# PLD_Controller_Board.net
KiCad netlist of a schematic drawn in EAGLE
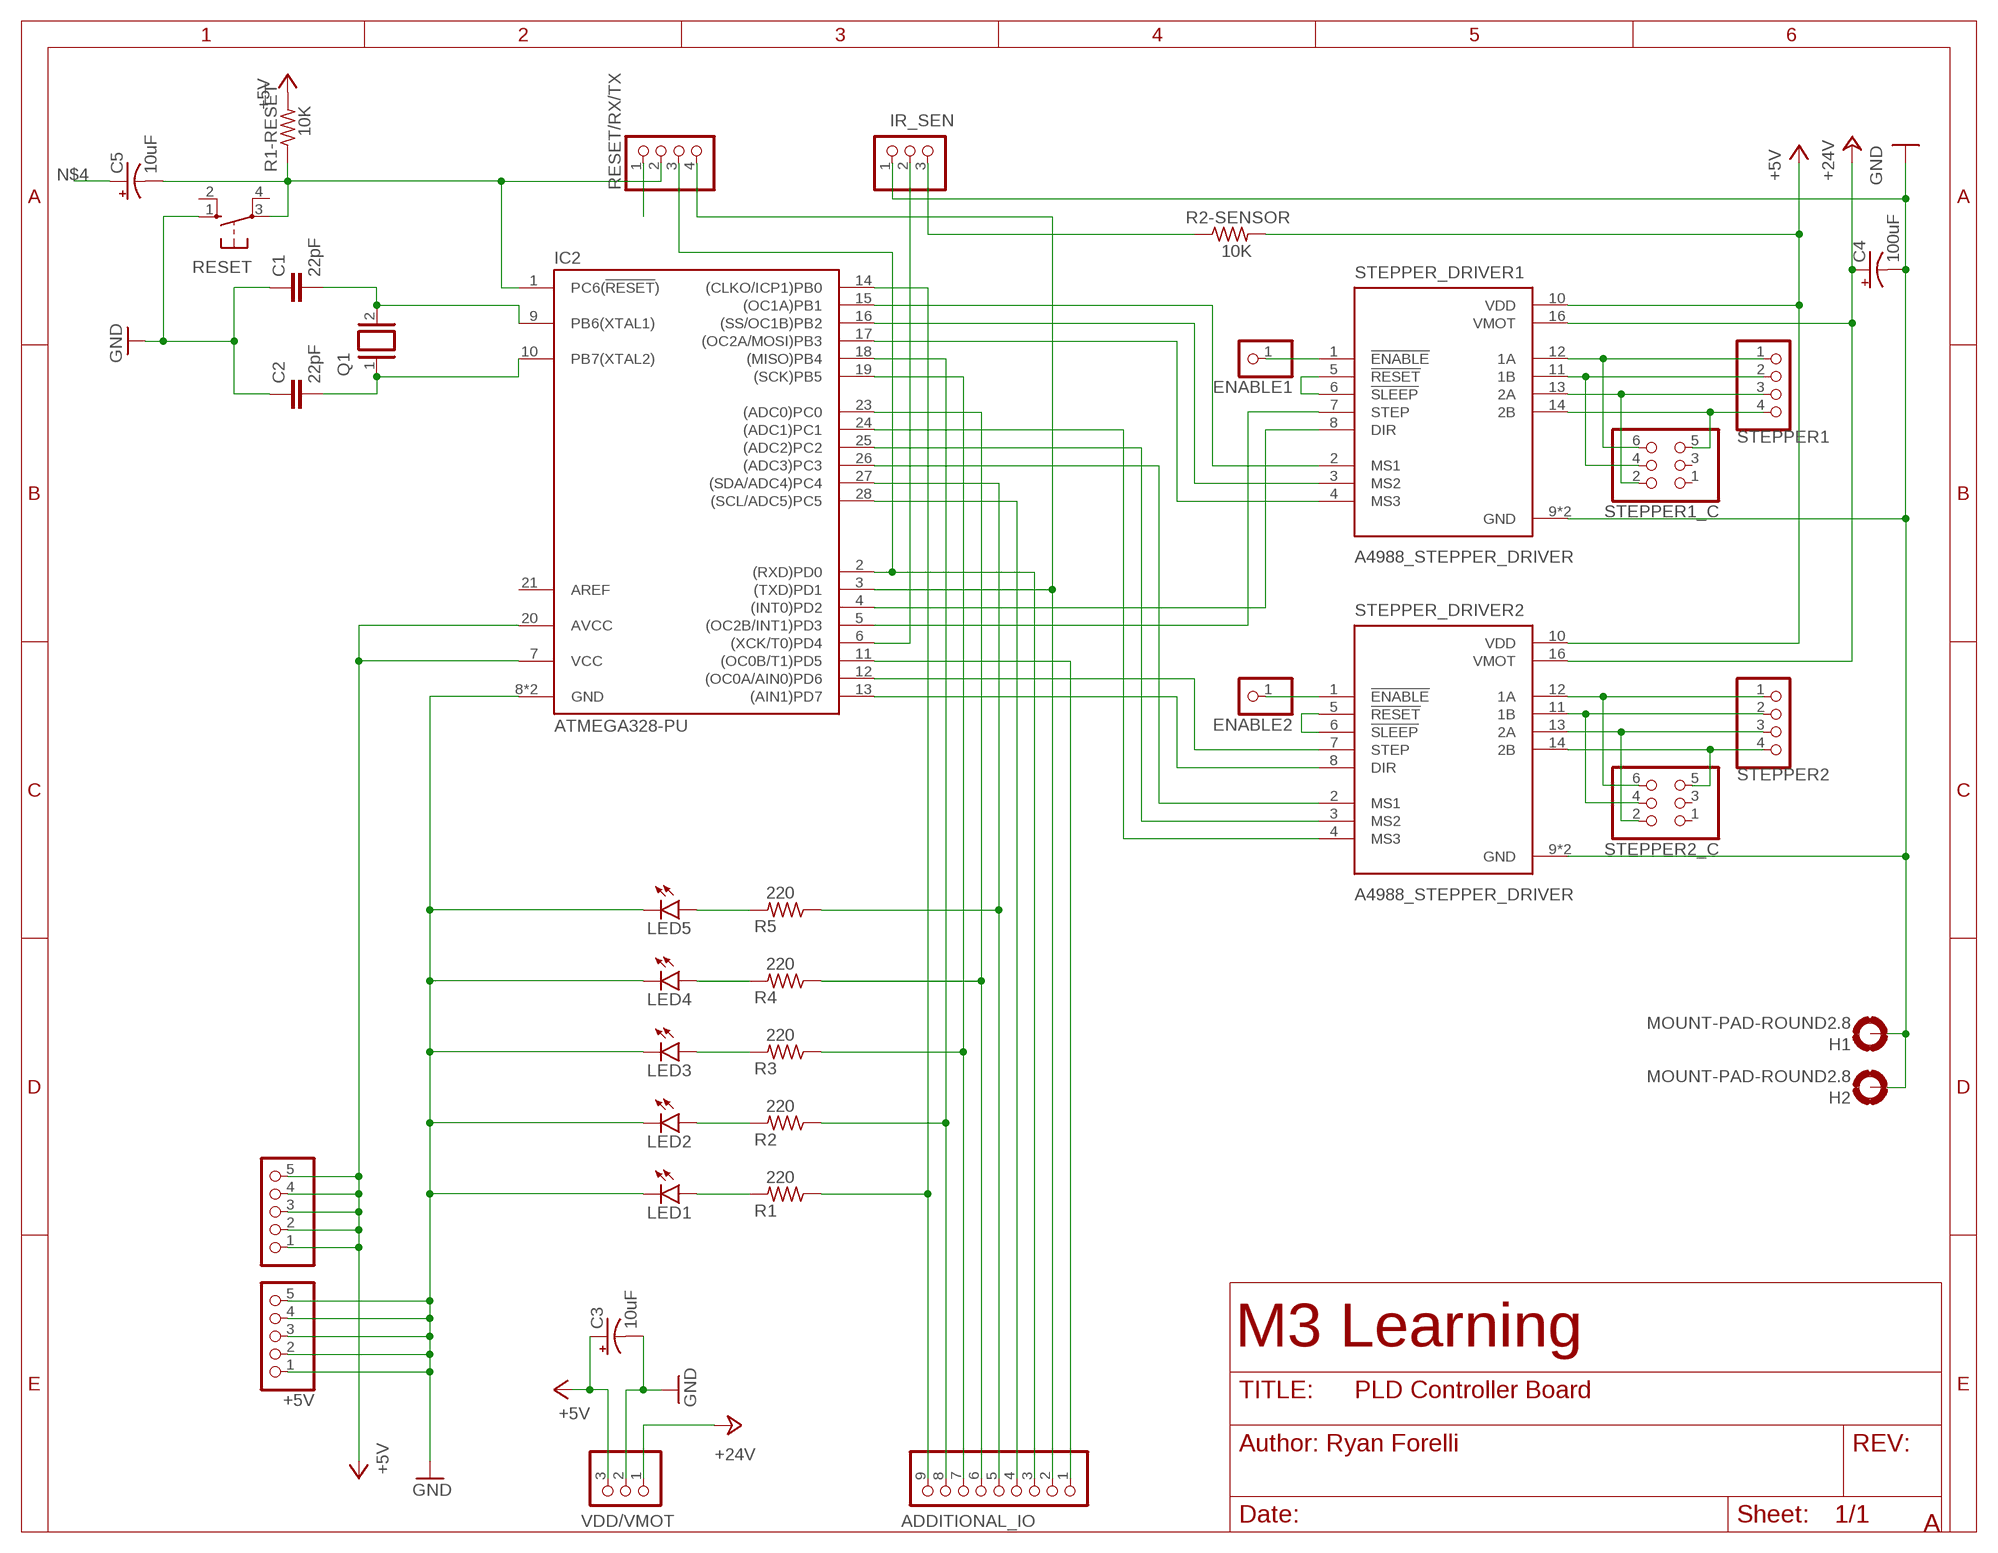
[diagram p0: schematic, sheet 1]

(export (version "E")
  (design (tool "Eeschema 10.0.6"))
  (components
    (comp (ref "+5V")
      (value "PINHD-1X5")
      (footprint "eagle-import:1X05")
      (libsource (lib "eagle-import") (part "PINHD-1X5"))
    )
    (comp (ref "ADDITIONAL_IO")
      (value "PINHD-1X9")
      (footprint "eagle-import:1X09")
      (libsource (lib "eagle-import") (part "PINHD-1X9"))
    )
    (comp (ref "C1")
      (value "22pF")
      (footprint "eagle-import:CAP-PTH-2.54")
      (libsource (lib "eagle-import") (part "22PF-PTH-2.54MM-200V-5%"))
    )
    (comp (ref "C2")
      (value "22pF")
      (footprint "eagle-import:CAP-PTH-2.54")
      (libsource (lib "eagle-import") (part "22PF-PTH-2.54MM-200V-5%"))
    )
    (comp (ref "C3")
      (value "10uF")
      (footprint "eagle-import:CPOL-RADIAL-2.5MM-5MM")
      (libsource (lib "eagle-import") (part "10UF-POLAR-RADIAL-2.5MM-25V-20%"))
    )
    (comp (ref "C4")
      (value "100uF")
      (footprint "eagle-import:CPOL-RADIAL-2.5MM-5MM")
      (libsource (lib "eagle-import") (part "10UF-POLAR-RADIAL-2.5MM-25V-20%"))
    )
    (comp (ref "C5")
      (value "10uF")
      (footprint "eagle-import:CPOL-RADIAL-2.5MM-5MM")
      (libsource (lib "eagle-import") (part "10UF-POLAR-RADIAL-2.5MM-25V-20%"))
    )
    (comp (ref "ENABLE1")
      (value "PINHD-1X1")
      (footprint "eagle-import:1X01")
      (libsource (lib "eagle-import") (part "PINHD-1X1"))
    )
    (comp (ref "ENABLE2")
      (value "PINHD-1X1")
      (footprint "eagle-import:1X01")
      (libsource (lib "eagle-import") (part "PINHD-1X1"))
    )
    (comp (ref "GND")
      (value "PINHD-1X5")
      (footprint "eagle-import:1X05")
      (libsource (lib "eagle-import") (part "PINHD-1X5"))
    )
    (comp (ref "H1")
      (value "MOUNT-PAD-ROUND2.8")
      (footprint "eagle-import:2,8-PAD")
      (libsource (lib "eagle-import") (part "MOUNT-PAD-ROUND2.8"))
    )
    (comp (ref "H2")
      (value "MOUNT-PAD-ROUND2.8")
      (footprint "eagle-import:2,8-PAD")
      (libsource (lib "eagle-import") (part "MOUNT-PAD-ROUND2.8"))
    )
    (comp (ref "IC2")
      (value "ATMEGA328-PU")
      (footprint "eagle-import:DIL28")
      (fields (field (name "MF") "Microchip Technology"))
      (libsource (lib "eagle-import") (part "ATMEGA328-PU"))
    )
    (comp (ref "IR_SEN")
      (value "PINHD-1X3")
      (footprint "eagle-import:1X03")
      (libsource (lib "eagle-import") (part "PINHD-1X3"))
    )
    (comp (ref "LED1")
      (value "LED5MM")
      (footprint "eagle-import:LED5MM")
      (libsource (lib "eagle-import") (part "LED5MM"))
    )
    (comp (ref "LED2")
      (value "LED5MM")
      (footprint "eagle-import:LED5MM")
      (libsource (lib "eagle-import") (part "LED5MM"))
    )
    (comp (ref "LED3")
      (value "LED5MM")
      (footprint "eagle-import:LED5MM")
      (libsource (lib "eagle-import") (part "LED5MM"))
    )
    (comp (ref "LED4")
      (value "LED5MM")
      (footprint "eagle-import:LED5MM")
      (libsource (lib "eagle-import") (part "LED5MM"))
    )
    (comp (ref "LED5")
      (value "LED5MM")
      (footprint "eagle-import:LED5MM")
      (libsource (lib "eagle-import") (part "LED5MM"))
    )
    (comp (ref "Q1")
      (value "XTAL/S")
      (footprint "eagle-import:QS")
      (libsource (lib "eagle-import") (part "XTAL/S"))
    )
    (comp (ref "R1")
      (value "220")
      (footprint "eagle-import:0204_7")
      (libsource (lib "eagle-import") (part "R-US_0204/7"))
    )
    (comp (ref "R1-RESET")
      (value "10K")
      (footprint "eagle-import:0204_7")
      (libsource (lib "eagle-import") (part "R-US_0204/7"))
    )
    (comp (ref "R2")
      (value "220")
      (footprint "eagle-import:0204_7")
      (libsource (lib "eagle-import") (part "R-US_0204/7"))
    )
    (comp (ref "R2-SENSOR")
      (value "10K")
      (footprint "eagle-import:0204_7")
      (libsource (lib "eagle-import") (part "R-US_0204/7"))
    )
    (comp (ref "R3")
      (value "220")
      (footprint "eagle-import:0204_7")
      (libsource (lib "eagle-import") (part "R-US_0204/7"))
    )
    (comp (ref "R4")
      (value "220")
      (footprint "eagle-import:0204_7")
      (libsource (lib "eagle-import") (part "R-US_0204/7"))
    )
    (comp (ref "R5")
      (value "220")
      (footprint "eagle-import:0204_7")
      (libsource (lib "eagle-import") (part "R-US_0204/7"))
    )
    (comp (ref "RESET")
      (value "10-XX")
      (footprint "eagle-import:B3F-10XX")
      (fields (field (name "MPN") "B3F-1000"))
      (libsource (lib "eagle-import") (part "10-XX"))
    )
    (comp (ref "RESET/RX/TX")
      (value "PINHD-1X4")
      (footprint "eagle-import:1X04")
      (libsource (lib "eagle-import") (part "PINHD-1X4"))
    )
    (comp (ref "STEPPER1")
      (value "PINHD-1X4")
      (footprint "eagle-import:1X04")
      (libsource (lib "eagle-import") (part "PINHD-1X4"))
    )
    (comp (ref "STEPPER1_C")
      (value "PINHD-2X3")
      (footprint "eagle-import:2X03")
      (libsource (lib "eagle-import") (part "PINHD-2X3"))
    )
    (comp (ref "STEPPER2")
      (value "PINHD-1X4")
      (footprint "eagle-import:1X04")
      (libsource (lib "eagle-import") (part "PINHD-1X4"))
    )
    (comp (ref "STEPPER2_C")
      (value "PINHD-2X3")
      (footprint "eagle-import:2X03")
      (libsource (lib "eagle-import") (part "PINHD-2X3"))
    )
    (comp (ref "STEPPER_DRIVER1")
      (value "A4988_STEPPER_DRIVER")
      (footprint "eagle-import:MODULE_A4988_STEPPER_MOTOR_DRIVER_CARRIER")
      (fields (field (name "MF") "Pololu") (field (name "MP") "A4988 STEPPER MOTOR DRIVER CARRIER"))
      (libsource (lib "eagle-import") (part "A4988_STEPPER_MOTOR_DRIVER_CARRIER"))
    )
    (comp (ref "STEPPER_DRIVER2")
      (value "A4988_STEPPER_DRIVER")
      (footprint "eagle-import:MODULE_A4988_STEPPER_MOTOR_DRIVER_CARRIER")
      (fields (field (name "MF") "Pololu") (field (name "MP") "A4988 STEPPER MOTOR DRIVER CARRIER"))
      (libsource (lib "eagle-import") (part "A4988_STEPPER_MOTOR_DRIVER_CARRIER"))
    )
    (comp (ref "VDD/VMOT")
      (value "PINHD-1X3")
      (footprint "eagle-import:1X03")
      (libsource (lib "eagle-import") (part "PINHD-1X3"))
    )
  )
  (nets
    (net (code "1") (name "+5V") (class "Default")
      (node (ref "C3") (pin "1") (pinfunction "+_1") (pintype "passive"))
      (node (ref "GND") (pin "1") (pinfunction "1_1") (pintype "passive"))
      (node (ref "GND") (pin "2") (pinfunction "2_2") (pintype "passive"))
      (node (ref "GND") (pin "3") (pinfunction "3_3") (pintype "passive"))
      (node (ref "GND") (pin "4") (pinfunction "4_4") (pintype "passive"))
      (node (ref "GND") (pin "5") (pinfunction "5_5") (pintype "passive"))
      (node (ref "IC2") (pin "20") (pinfunction "AVCC_20") (pintype "power_in"))
      (node (ref "IC2") (pin "7") (pinfunction "VCC_7") (pintype "power_in"))
      (node (ref "R1-RESET") (pin "2") (pinfunction "2_2") (pintype "passive"))
      (node (ref "R2-SENSOR") (pin "2") (pinfunction "2_2") (pintype "passive"))
      (node (ref "STEPPER_DRIVER1") (pin "10") (pinfunction "VDD_10") (pintype "power_in"))
      (node (ref "STEPPER_DRIVER2") (pin "10") (pinfunction "VDD_10") (pintype "power_in"))
      (node (ref "VDD/VMOT") (pin "3") (pinfunction "3_3") (pintype "passive"))
    )
    (net (code "2") (name "+24V") (class "Default")
      (node (ref "C4") (pin "1") (pinfunction "+_1") (pintype "passive"))
      (node (ref "STEPPER_DRIVER1") (pin "16") (pinfunction "VMOT_16") (pintype "power_in"))
      (node (ref "STEPPER_DRIVER2") (pin "16") (pinfunction "VMOT_16") (pintype "power_in"))
      (node (ref "VDD/VMOT") (pin "1") (pinfunction "1_1") (pintype "passive"))
    )
    (net (code "3") (name "/N$4") (class "Default")
      (node (ref "C5") (pin "1") (pinfunction "+_1") (pintype "passive"))
      (node (ref "RESET/RX/TX") (pin "1") (pinfunction "1_1") (pintype "passive"))
    )
    (net (code "4") (name "GND") (class "Default")
      (node (ref "+5V") (pin "1") (pinfunction "1_1") (pintype "passive"))
      (node (ref "+5V") (pin "2") (pinfunction "2_2") (pintype "passive"))
      (node (ref "+5V") (pin "3") (pinfunction "3_3") (pintype "passive"))
      (node (ref "+5V") (pin "4") (pinfunction "4_4") (pintype "passive"))
      (node (ref "+5V") (pin "5") (pinfunction "5_5") (pintype "passive"))
      (node (ref "C1") (pin "1") (pinfunction "1_1") (pintype "passive"))
      (node (ref "C2") (pin "1") (pinfunction "1_1") (pintype "passive"))
      (node (ref "C3") (pin "2") (pinfunction "-_2") (pintype "passive"))
      (node (ref "C4") (pin "2") (pinfunction "-_2") (pintype "passive"))
      (node (ref "H1") (pin "B2,8") (pinfunction "MOUNT_B2,8") (pintype "passive"))
      (node (ref "H2") (pin "B2,8") (pinfunction "MOUNT_B2,8") (pintype "passive"))
      (node (ref "IC2") (pin "22") (pinfunction "GND_22") (pintype "power_in"))
      (node (ref "IC2") (pin "8") (pinfunction "GND_8") (pintype "power_in"))
      (node (ref "IR_SEN") (pin "1") (pinfunction "1_1") (pintype "passive"))
      (node (ref "LED1") (pin "K") (pinfunction "C_K") (pintype "passive"))
      (node (ref "LED2") (pin "K") (pinfunction "C_K") (pintype "passive"))
      (node (ref "LED3") (pin "K") (pinfunction "C_K") (pintype "passive"))
      (node (ref "LED4") (pin "K") (pinfunction "C_K") (pintype "passive"))
      (node (ref "LED5") (pin "K") (pinfunction "C_K") (pintype "passive"))
      (node (ref "RESET") (pin "1") (pinfunction "S_1") (pintype "passive"))
      (node (ref "STEPPER_DRIVER1") (pin "15") (pinfunction "GND_15") (pintype "power_in"))
      (node (ref "STEPPER_DRIVER1") (pin "9") (pinfunction "GND_9") (pintype "power_in"))
      (node (ref "STEPPER_DRIVER2") (pin "15") (pinfunction "GND_15") (pintype "power_in"))
      (node (ref "STEPPER_DRIVER2") (pin "9") (pinfunction "GND_9") (pintype "power_in"))
      (node (ref "VDD/VMOT") (pin "2") (pinfunction "2_2") (pintype "passive"))
    )
    (net (code "5") (name "Net-(C5--)") (class "Default")
      (node (ref "C5") (pin "2") (pinfunction "-_2") (pintype "passive"))
      (node (ref "IC2") (pin "1") (pinfunction "PC6(~{RESET})_1") (pintype "bidirectional"))
      (node (ref "R1-RESET") (pin "1") (pinfunction "1_1") (pintype "passive"))
      (node (ref "RESET") (pin "3") (pinfunction "P_3") (pintype "passive"))
      (node (ref "RESET/RX/TX") (pin "2") (pinfunction "2_2") (pintype "passive"))
    )
    (net (code "6") (name "Net-(IC2-(ADC0)PC0)") (class "Default")
      (node (ref "ADDITIONAL_IO") (pin "6") (pinfunction "6_6") (pintype "passive"))
      (node (ref "IC2") (pin "23") (pinfunction "(ADC0)PC0_23") (pintype "bidirectional"))
      (node (ref "R4") (pin "1") (pinfunction "1_1") (pintype "passive"))
    )
    (net (code "7") (name "Net-(IC2-(ADC1)PC1)") (class "Default")
      (node (ref "IC2") (pin "24") (pinfunction "(ADC1)PC1_24") (pintype "bidirectional"))
      (node (ref "STEPPER_DRIVER2") (pin "4") (pinfunction "MS3_4") (pintype "input"))
    )
    (net (code "8") (name "Net-(IC2-(ADC2)PC2)") (class "Default")
      (node (ref "IC2") (pin "25") (pinfunction "(ADC2)PC2_25") (pintype "bidirectional"))
      (node (ref "STEPPER_DRIVER2") (pin "3") (pinfunction "MS2_3") (pintype "input"))
    )
    (net (code "9") (name "Net-(IC2-(ADC3)PC3)") (class "Default")
      (node (ref "IC2") (pin "26") (pinfunction "(ADC3)PC3_26") (pintype "bidirectional"))
      (node (ref "STEPPER_DRIVER2") (pin "2") (pinfunction "MS1_2") (pintype "input"))
    )
    (net (code "10") (name "Net-(IC2-(AIN1)PD7)") (class "Default")
      (node (ref "IC2") (pin "13") (pinfunction "(AIN1)PD7_13") (pintype "bidirectional"))
      (node (ref "STEPPER_DRIVER2") (pin "8") (pinfunction "DIR_8") (pintype "input"))
    )
    (net (code "11") (name "Net-(IC2-(CLKO{slash}ICP1)PB0)") (class "Default")
      (node (ref "ADDITIONAL_IO") (pin "9") (pinfunction "9_9") (pintype "passive"))
      (node (ref "IC2") (pin "14") (pinfunction "(CLKO/ICP1)PB0_14") (pintype "bidirectional"))
      (node (ref "R1") (pin "1") (pinfunction "1_1") (pintype "passive"))
    )
    (net (code "12") (name "Net-(IC2-(INT0)PD2)") (class "Default")
      (node (ref "IC2") (pin "4") (pinfunction "(INT0)PD2_4") (pintype "bidirectional"))
      (node (ref "STEPPER_DRIVER1") (pin "8") (pinfunction "DIR_8") (pintype "input"))
    )
    (net (code "13") (name "Net-(IC2-(MISO)PB4)") (class "Default")
      (node (ref "ADDITIONAL_IO") (pin "8") (pinfunction "8_8") (pintype "passive"))
      (node (ref "IC2") (pin "18") (pinfunction "(MISO)PB4_18") (pintype "bidirectional"))
      (node (ref "R2") (pin "1") (pinfunction "1_1") (pintype "passive"))
    )
    (net (code "14") (name "Net-(IC2-(OC0A{slash}AIN0)PD6)") (class "Default")
      (node (ref "IC2") (pin "12") (pinfunction "(OC0A/AIN0)PD6_12") (pintype "bidirectional"))
      (node (ref "STEPPER_DRIVER2") (pin "7") (pinfunction "STEP_7") (pintype "input"))
    )
    (net (code "15") (name "Net-(IC2-(OC0B{slash}T1)PD5)") (class "Default")
      (node (ref "ADDITIONAL_IO") (pin "1") (pinfunction "1_1") (pintype "passive"))
      (node (ref "IC2") (pin "11") (pinfunction "(OC0B/T1)PD5_11") (pintype "bidirectional"))
    )
    (net (code "16") (name "Net-(IC2-(OC1A)PB1)") (class "Default")
      (node (ref "IC2") (pin "15") (pinfunction "(OC1A)PB1_15") (pintype "bidirectional"))
      (node (ref "STEPPER_DRIVER1") (pin "2") (pinfunction "MS1_2") (pintype "input"))
    )
    (net (code "17") (name "Net-(IC2-(OC2A{slash}MOSI)PB3)") (class "Default")
      (node (ref "IC2") (pin "17") (pinfunction "(OC2A/MOSI)PB3_17") (pintype "bidirectional"))
      (node (ref "STEPPER_DRIVER1") (pin "4") (pinfunction "MS3_4") (pintype "input"))
    )
    (net (code "18") (name "Net-(IC2-(OC2B{slash}INT1)PD3)") (class "Default")
      (node (ref "IC2") (pin "5") (pinfunction "(OC2B/INT1)PD3_5") (pintype "bidirectional"))
      (node (ref "STEPPER_DRIVER1") (pin "7") (pinfunction "STEP_7") (pintype "input"))
    )
    (net (code "19") (name "Net-(IC2-(RXD)PD0)") (class "Default")
      (node (ref "ADDITIONAL_IO") (pin "3") (pinfunction "3_3") (pintype "passive"))
      (node (ref "IC2") (pin "2") (pinfunction "(RXD)PD0_2") (pintype "bidirectional"))
      (node (ref "RESET/RX/TX") (pin "3") (pinfunction "3_3") (pintype "passive"))
    )
    (net (code "20") (name "Net-(IC2-(SCK)PB5)") (class "Default")
      (node (ref "ADDITIONAL_IO") (pin "7") (pinfunction "7_7") (pintype "passive"))
      (node (ref "IC2") (pin "19") (pinfunction "(SCK)PB5_19") (pintype "bidirectional"))
      (node (ref "R3") (pin "1") (pinfunction "1_1") (pintype "passive"))
    )
    (net (code "21") (name "Net-(IC2-(SCL{slash}ADC5)PC5)") (class "Default")
      (node (ref "ADDITIONAL_IO") (pin "4") (pinfunction "4_4") (pintype "passive"))
      (node (ref "IC2") (pin "28") (pinfunction "(SCL/ADC5)PC5_28") (pintype "bidirectional"))
    )
    (net (code "22") (name "Net-(IC2-(SDA{slash}ADC4)PC4)") (class "Default")
      (node (ref "ADDITIONAL_IO") (pin "5") (pinfunction "5_5") (pintype "passive"))
      (node (ref "IC2") (pin "27") (pinfunction "(SDA/ADC4)PC4_27") (pintype "bidirectional"))
      (node (ref "R5") (pin "1") (pinfunction "1_1") (pintype "passive"))
    )
    (net (code "23") (name "Net-(IC2-(SS{slash}OC1B)PB2)") (class "Default")
      (node (ref "IC2") (pin "16") (pinfunction "(SS/OC1B)PB2_16") (pintype "bidirectional"))
      (node (ref "STEPPER_DRIVER1") (pin "3") (pinfunction "MS2_3") (pintype "input"))
    )
    (net (code "24") (name "Net-(IC2-(TXD)PD1)") (class "Default")
      (node (ref "ADDITIONAL_IO") (pin "2") (pinfunction "2_2") (pintype "passive"))
      (node (ref "IC2") (pin "3") (pinfunction "(TXD)PD1_3") (pintype "bidirectional"))
      (node (ref "RESET/RX/TX") (pin "4") (pinfunction "4_4") (pintype "passive"))
    )
    (net (code "25") (name "Net-(IC2-(XCK{slash}T0)PD4)") (class "Default")
      (node (ref "IC2") (pin "6") (pinfunction "(XCK/T0)PD4_6") (pintype "bidirectional"))
      (node (ref "IR_SEN") (pin "2") (pinfunction "2_2") (pintype "passive"))
    )
    (net (code "26") (name "Net-(IC2-PB6(XTAL1))") (class "Default")
      (node (ref "C1") (pin "2") (pinfunction "2_2") (pintype "passive"))
      (node (ref "IC2") (pin "9") (pinfunction "PB6(XTAL1)_9") (pintype "bidirectional"))
      (node (ref "Q1") (pin "2") (pinfunction "2_2") (pintype "passive"))
    )
    (net (code "27") (name "Net-(IC2-PB7(XTAL2))") (class "Default")
      (node (ref "C2") (pin "2") (pinfunction "2_2") (pintype "passive"))
      (node (ref "IC2") (pin "10") (pinfunction "PB7(XTAL2)_10") (pintype "bidirectional"))
      (node (ref "Q1") (pin "1") (pinfunction "1_1") (pintype "passive"))
    )
    (net (code "28") (name "Net-(IR_SEN-Pad3)") (class "Default")
      (node (ref "IR_SEN") (pin "3") (pinfunction "3_3") (pintype "passive"))
      (node (ref "R2-SENSOR") (pin "1") (pinfunction "1_1") (pintype "passive"))
    )
    (net (code "29") (name "Net-(LED1-PadA)") (class "Default")
      (node (ref "LED1") (pin "A") (pinfunction "A_A") (pintype "passive"))
      (node (ref "R1") (pin "2") (pinfunction "2_2") (pintype "passive"))
    )
    (net (code "30") (name "Net-(LED2-PadA)") (class "Default")
      (node (ref "LED2") (pin "A") (pinfunction "A_A") (pintype "passive"))
      (node (ref "R2") (pin "2") (pinfunction "2_2") (pintype "passive"))
    )
    (net (code "31") (name "Net-(LED3-PadA)") (class "Default")
      (node (ref "LED3") (pin "A") (pinfunction "A_A") (pintype "passive"))
      (node (ref "R3") (pin "2") (pinfunction "2_2") (pintype "passive"))
    )
    (net (code "32") (name "Net-(LED4-PadA)") (class "Default")
      (node (ref "LED4") (pin "A") (pinfunction "A_A") (pintype "passive"))
      (node (ref "R4") (pin "2") (pinfunction "2_2") (pintype "passive"))
    )
    (net (code "33") (name "Net-(LED5-PadA)") (class "Default")
      (node (ref "LED5") (pin "A") (pinfunction "A_A") (pintype "passive"))
      (node (ref "R5") (pin "2") (pinfunction "2_2") (pintype "passive"))
    )
    (net (code "34") (name "Net-(STEPPER_DRIVER1-1A)") (class "Default")
      (node (ref "STEPPER1") (pin "1") (pinfunction "1_1") (pintype "passive"))
      (node (ref "STEPPER1_C") (pin "6") (pinfunction "6_6") (pintype "passive"))
      (node (ref "STEPPER_DRIVER1") (pin "12") (pinfunction "1A_12") (pintype "output"))
    )
    (net (code "35") (name "Net-(STEPPER_DRIVER1-1B)") (class "Default")
      (node (ref "STEPPER1") (pin "2") (pinfunction "2_2") (pintype "passive"))
      (node (ref "STEPPER1_C") (pin "4") (pinfunction "4_4") (pintype "passive"))
      (node (ref "STEPPER_DRIVER1") (pin "11") (pinfunction "1B_11") (pintype "output"))
    )
    (net (code "36") (name "Net-(STEPPER_DRIVER1-2A)") (class "Default")
      (node (ref "STEPPER1") (pin "3") (pinfunction "3_3") (pintype "passive"))
      (node (ref "STEPPER1_C") (pin "2") (pinfunction "2_2") (pintype "passive"))
      (node (ref "STEPPER_DRIVER1") (pin "13") (pinfunction "2A_13") (pintype "output"))
    )
    (net (code "37") (name "Net-(STEPPER_DRIVER1-2B)") (class "Default")
      (node (ref "STEPPER1") (pin "4") (pinfunction "4_4") (pintype "passive"))
      (node (ref "STEPPER1_C") (pin "5") (pinfunction "5_5") (pintype "passive"))
      (node (ref "STEPPER_DRIVER1") (pin "14") (pinfunction "2B_14") (pintype "output"))
    )
    (net (code "38") (name "Net-(STEPPER_DRIVER1-~{ENABLE})") (class "Default")
      (node (ref "ENABLE1") (pin "1") (pinfunction "1_1") (pintype "passive"))
      (node (ref "STEPPER_DRIVER1") (pin "1") (pinfunction "~{ENABLE}_1") (pintype "input"))
    )
    (net (code "39") (name "Net-(STEPPER_DRIVER1-~{RESET})") (class "Default")
      (node (ref "STEPPER_DRIVER1") (pin "5") (pinfunction "~{RESET}_5") (pintype "input"))
      (node (ref "STEPPER_DRIVER1") (pin "6") (pinfunction "~{SLEEP}_6") (pintype "input"))
    )
    (net (code "40") (name "Net-(STEPPER_DRIVER2-1A)") (class "Default")
      (node (ref "STEPPER2") (pin "1") (pinfunction "1_1") (pintype "passive"))
      (node (ref "STEPPER2_C") (pin "6") (pinfunction "6_6") (pintype "passive"))
      (node (ref "STEPPER_DRIVER2") (pin "12") (pinfunction "1A_12") (pintype "output"))
    )
    (net (code "41") (name "Net-(STEPPER_DRIVER2-1B)") (class "Default")
      (node (ref "STEPPER2") (pin "2") (pinfunction "2_2") (pintype "passive"))
      (node (ref "STEPPER2_C") (pin "4") (pinfunction "4_4") (pintype "passive"))
      (node (ref "STEPPER_DRIVER2") (pin "11") (pinfunction "1B_11") (pintype "output"))
    )
    (net (code "42") (name "Net-(STEPPER_DRIVER2-2A)") (class "Default")
      (node (ref "STEPPER2") (pin "3") (pinfunction "3_3") (pintype "passive"))
      (node (ref "STEPPER2_C") (pin "2") (pinfunction "2_2") (pintype "passive"))
      (node (ref "STEPPER_DRIVER2") (pin "13") (pinfunction "2A_13") (pintype "output"))
    )
    (net (code "43") (name "Net-(STEPPER_DRIVER2-2B)") (class "Default")
      (node (ref "STEPPER2") (pin "4") (pinfunction "4_4") (pintype "passive"))
      (node (ref "STEPPER2_C") (pin "5") (pinfunction "5_5") (pintype "passive"))
      (node (ref "STEPPER_DRIVER2") (pin "14") (pinfunction "2B_14") (pintype "output"))
    )
    (net (code "44") (name "Net-(STEPPER_DRIVER2-~{ENABLE})") (class "Default")
      (node (ref "ENABLE2") (pin "1") (pinfunction "1_1") (pintype "passive"))
      (node (ref "STEPPER_DRIVER2") (pin "1") (pinfunction "~{ENABLE}_1") (pintype "input"))
    )
    (net (code "45") (name "Net-(STEPPER_DRIVER2-~{RESET})") (class "Default")
      (node (ref "STEPPER_DRIVER2") (pin "5") (pinfunction "~{RESET}_5") (pintype "input"))
      (node (ref "STEPPER_DRIVER2") (pin "6") (pinfunction "~{SLEEP}_6") (pintype "input"))
    )
    (net (code "46") (name "unconnected-(IC2-AREF-Pad21)") (class "Default")
      (node (ref "IC2") (pin "21") (pinfunction "AREF_21") (pintype "passive"))
    )
    (net (code "47") (name "unconnected-(RESET-P1-Pad4)") (class "Default")
      (node (ref "RESET") (pin "4") (pinfunction "P1_4") (pintype "passive"))
    )
    (net (code "48") (name "unconnected-(RESET-S1-Pad2)") (class "Default")
      (node (ref "RESET") (pin "2") (pinfunction "S1_2") (pintype "passive"))
    )
    (net (code "49") (name "unconnected-(STEPPER1_C-Pad1)") (class "Default")
      (node (ref "STEPPER1_C") (pin "1") (pinfunction "1_1") (pintype "passive"))
    )
    (net (code "50") (name "unconnected-(STEPPER1_C-Pad3)") (class "Default")
      (node (ref "STEPPER1_C") (pin "3") (pinfunction "3_3") (pintype "passive"))
    )
    (net (code "51") (name "unconnected-(STEPPER2_C-Pad1)") (class "Default")
      (node (ref "STEPPER2_C") (pin "1") (pinfunction "1_1") (pintype "passive"))
    )
    (net (code "52") (name "unconnected-(STEPPER2_C-Pad3)") (class "Default")
      (node (ref "STEPPER2_C") (pin "3") (pinfunction "3_3") (pintype "passive"))
    )
  )
)
